# 01-MAIN.net
KiCad netlist of a schematic drawn in Altium Designer
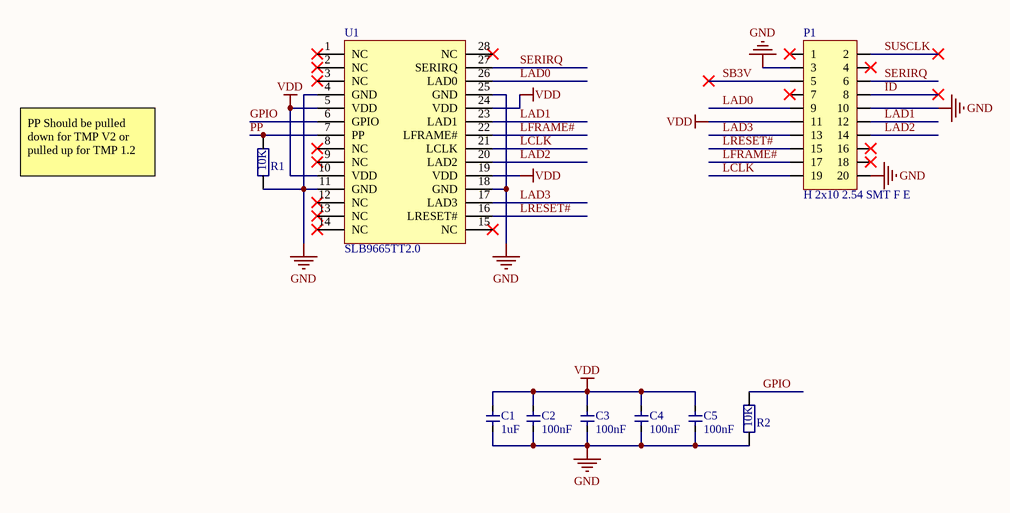
[diagram p0: 01-MAIN.SchDoc]

(export (version "E")
  (design (tool "Eeschema 10.0.6"))
  (components
    (comp (ref "C1")
      (value "1uF")
      (footprint "C0805")
      (description "Ceramic capacitor")
      (fields (field (name "VOLTAGE") "25V"))
      (libsource (lib "Shelestov_Capacitors") (part "C0805_1uF_25V"))
    )
    (comp (ref "C2")
      (value "100nF")
      (footprint "C0603_NOSILK")
      (description "Ceramic capacitor")
      (fields (field (name "VOLTAGE") "16V") (field (name "MF") "YAGEO"))
      (libsource (lib "Shelestov_Capacitors") (part "C0603_100nF_16V"))
    )
    (comp (ref "C3")
      (value "100nF")
      (footprint "C0603_NOSILK")
      (description "Ceramic capacitor")
      (fields (field (name "VOLTAGE") "16V") (field (name "MF") "YAGEO"))
      (libsource (lib "Shelestov_Capacitors") (part "C0603_100nF_16V"))
    )
    (comp (ref "C4")
      (value "100nF")
      (footprint "C0603_NOSILK")
      (description "Ceramic capacitor")
      (fields (field (name "VOLTAGE") "16V") (field (name "MF") "YAGEO"))
      (libsource (lib "Shelestov_Capacitors") (part "C0603_100nF_16V"))
    )
    (comp (ref "C5")
      (value "100nF")
      (footprint "C0603_NOSILK")
      (description "Ceramic capacitor")
      (fields (field (name "VOLTAGE") "16V") (field (name "MF") "YAGEO"))
      (libsource (lib "Shelestov_Capacitors") (part "C0603_100nF_16V"))
    )
    (comp (ref "P1")
      (value "H 2x10 2.54 SMT F E")
      (footprint "HEADER 2x10 2.54 SMT FEMALE EDGE")
      (libsource (lib "Shelestov_Connectors") (part "H 2x10 2.54 SMT F E"))
    )
    (comp (ref "R1")
      (value "~")
      (footprint "R0603_NOSILK")
      (description "Resistor General")
      (fields (field (name "TOLERANCE") "5%") (field (name "RESISTANCE") "10K"))
      (libsource (lib "Shelestov_Resistors") (part "R0603_10K"))
    )
    (comp (ref "R2")
      (value "~")
      (footprint "R0603_NOSILK")
      (description "Resistor General")
      (fields (field (name "TOLERANCE") "5%") (field (name "RESISTANCE") "10K"))
      (libsource (lib "Shelestov_Resistors") (part "R0603_10K"))
    )
    (comp (ref "U1")
      (value "SLB9665TT2.0")
      (footprint "TSSOP-28-2")
      (description "TPM SLB 9665 TPM2.0 Trusted Platform Module")
      (libsource (lib "Shelestov_IC") (part "SLB9665TT2.0"))
    )
  )
  (nets
    (net (code "1") (name "/GPIO") (class "Default")
      (node (ref "R2") (pin "2") (pinfunction "2_2") (pintype "passive"))
      (node (ref "U1") (pin "6") (pinfunction "GPIO_6") (pintype "passive"))
    )
    (net (code "2") (name "/ID") (class "Default")
      (node (ref "P1") (pin "8") (pinfunction "8_8") (pintype "passive+no_connect"))
    )
    (net (code "3") (name "/LAD0") (class "Default")
      (node (ref "P1") (pin "9") (pinfunction "9_9") (pintype "passive"))
      (node (ref "U1") (pin "26") (pinfunction "LAD0_26") (pintype "passive"))
    )
    (net (code "4") (name "/LAD1") (class "Default")
      (node (ref "P1") (pin "12") (pinfunction "12_12") (pintype "passive"))
      (node (ref "U1") (pin "23") (pinfunction "LAD1_23") (pintype "passive"))
    )
    (net (code "5") (name "/LAD2") (class "Default")
      (node (ref "P1") (pin "14") (pinfunction "14_14") (pintype "passive"))
      (node (ref "U1") (pin "20") (pinfunction "LAD2_20") (pintype "passive"))
    )
    (net (code "6") (name "/LAD3") (class "Default")
      (node (ref "P1") (pin "13") (pinfunction "13_13") (pintype "passive"))
      (node (ref "U1") (pin "17") (pinfunction "LAD3_17") (pintype "passive"))
    )
    (net (code "7") (name "/LCLK") (class "Default")
      (node (ref "P1") (pin "19") (pinfunction "19_19") (pintype "passive"))
      (node (ref "U1") (pin "21") (pinfunction "LCLK_21") (pintype "passive"))
    )
    (net (code "8") (name "/LFRAME#") (class "Default")
      (node (ref "P1") (pin "17") (pinfunction "17_17") (pintype "passive"))
      (node (ref "U1") (pin "22") (pinfunction "LFRAME#_22") (pintype "passive"))
    )
    (net (code "9") (name "/LRESET#") (class "Default")
      (node (ref "P1") (pin "15") (pinfunction "15_15") (pintype "passive"))
      (node (ref "U1") (pin "16") (pinfunction "LRESET#_16") (pintype "passive"))
    )
    (net (code "10") (name "/PP") (class "Default")
      (node (ref "R1") (pin "2") (pinfunction "2_2") (pintype "passive"))
      (node (ref "U1") (pin "7") (pinfunction "PP_7") (pintype "passive"))
    )
    (net (code "11") (name "/SB3V") (class "Default")
      (node (ref "P1") (pin "5") (pinfunction "5_5") (pintype "passive+no_connect"))
    )
    (net (code "12") (name "/SERIRQ") (class "Default")
      (node (ref "P1") (pin "6") (pinfunction "6_6") (pintype "passive"))
      (node (ref "U1") (pin "27") (pinfunction "SERIRQ_27") (pintype "passive"))
    )
    (net (code "13") (name "/SUSCLK") (class "Default")
      (node (ref "P1") (pin "2") (pinfunction "2_2") (pintype "passive+no_connect"))
    )
    (net (code "14") (name "GND") (class "Default")
      (node (ref "C1") (pin "1") (pinfunction "1_1") (pintype "passive"))
      (node (ref "C2") (pin "1") (pinfunction "1_1") (pintype "passive"))
      (node (ref "C3") (pin "1") (pinfunction "1_1") (pintype "passive"))
      (node (ref "C4") (pin "1") (pinfunction "1_1") (pintype "passive"))
      (node (ref "C5") (pin "1") (pinfunction "1_1") (pintype "passive"))
      (node (ref "P1") (pin "10") (pinfunction "10_10") (pintype "passive"))
      (node (ref "P1") (pin "20") (pinfunction "20_20") (pintype "passive"))
      (node (ref "P1") (pin "3") (pinfunction "3_3") (pintype "passive"))
      (node (ref "R1") (pin "1") (pinfunction "1_1") (pintype "passive"))
      (node (ref "R2") (pin "1") (pinfunction "1_1") (pintype "passive"))
      (node (ref "U1") (pin "11") (pinfunction "GND_11") (pintype "power_in"))
      (node (ref "U1") (pin "18") (pinfunction "GND_18") (pintype "power_in"))
      (node (ref "U1") (pin "25") (pinfunction "GND_25") (pintype "power_in"))
      (node (ref "U1") (pin "4") (pinfunction "GND_4") (pintype "power_in"))
    )
    (net (code "15") (name "VDD") (class "Default")
      (node (ref "C1") (pin "2") (pinfunction "2_2") (pintype "passive"))
      (node (ref "C2") (pin "2") (pinfunction "2_2") (pintype "passive"))
      (node (ref "C3") (pin "2") (pinfunction "2_2") (pintype "passive"))
      (node (ref "C4") (pin "2") (pinfunction "2_2") (pintype "passive"))
      (node (ref "C5") (pin "2") (pinfunction "2_2") (pintype "passive"))
      (node (ref "P1") (pin "11") (pinfunction "11_11") (pintype "passive"))
      (node (ref "U1") (pin "10") (pinfunction "VDD_10") (pintype "power_in"))
      (node (ref "U1") (pin "19") (pinfunction "VDD_19") (pintype "power_in"))
      (node (ref "U1") (pin "24") (pinfunction "VDD_24") (pintype "power_in"))
      (node (ref "U1") (pin "5") (pinfunction "VDD_5") (pintype "power_in"))
    )
    (net (code "16") (name "unconnected-(P1-Pad1)") (class "Default")
      (node (ref "P1") (pin "1") (pinfunction "1_1") (pintype "passive+no_connect"))
    )
    (net (code "17") (name "unconnected-(P1-Pad4)") (class "Default")
      (node (ref "P1") (pin "4") (pinfunction "4_4") (pintype "passive+no_connect"))
    )
    (net (code "18") (name "unconnected-(P1-Pad7)") (class "Default")
      (node (ref "P1") (pin "7") (pinfunction "7_7") (pintype "passive+no_connect"))
    )
    (net (code "19") (name "unconnected-(P1-Pad16)") (class "Default")
      (node (ref "P1") (pin "16") (pinfunction "16_16") (pintype "passive+no_connect"))
    )
    (net (code "20") (name "unconnected-(P1-Pad18)") (class "Default")
      (node (ref "P1") (pin "18") (pinfunction "18_18") (pintype "passive+no_connect"))
    )
    (net (code "21") (name "unconnected-(U1-NC-Pad1)") (class "Default")
      (node (ref "U1") (pin "1") (pinfunction "NC_1") (pintype "passive+no_connect"))
    )
    (net (code "22") (name "unconnected-(U1-NC-Pad2)") (class "Default")
      (node (ref "U1") (pin "2") (pinfunction "NC_2") (pintype "passive+no_connect"))
    )
    (net (code "23") (name "unconnected-(U1-NC-Pad3)") (class "Default")
      (node (ref "U1") (pin "3") (pinfunction "NC_3") (pintype "passive+no_connect"))
    )
    (net (code "24") (name "unconnected-(U1-NC-Pad8)") (class "Default")
      (node (ref "U1") (pin "8") (pinfunction "NC_8") (pintype "passive+no_connect"))
    )
    (net (code "25") (name "unconnected-(U1-NC-Pad9)") (class "Default")
      (node (ref "U1") (pin "9") (pinfunction "NC_9") (pintype "passive+no_connect"))
    )
    (net (code "26") (name "unconnected-(U1-NC-Pad12)") (class "Default")
      (node (ref "U1") (pin "12") (pinfunction "NC_12") (pintype "passive+no_connect"))
    )
    (net (code "27") (name "unconnected-(U1-NC-Pad13)") (class "Default")
      (node (ref "U1") (pin "13") (pinfunction "NC_13") (pintype "passive+no_connect"))
    )
    (net (code "28") (name "unconnected-(U1-NC-Pad14)") (class "Default")
      (node (ref "U1") (pin "14") (pinfunction "NC_14") (pintype "passive+no_connect"))
    )
    (net (code "29") (name "unconnected-(U1-NC-Pad15)") (class "Default")
      (node (ref "U1") (pin "15") (pinfunction "NC_15") (pintype "passive+no_connect"))
    )
    (net (code "30") (name "unconnected-(U1-NC-Pad28)") (class "Default")
      (node (ref "U1") (pin "28") (pinfunction "NC_28") (pintype "passive+no_connect"))
    )
  )
)
